# shoeKicking.net
KiCad netlist of a schematic drawn in EAGLE
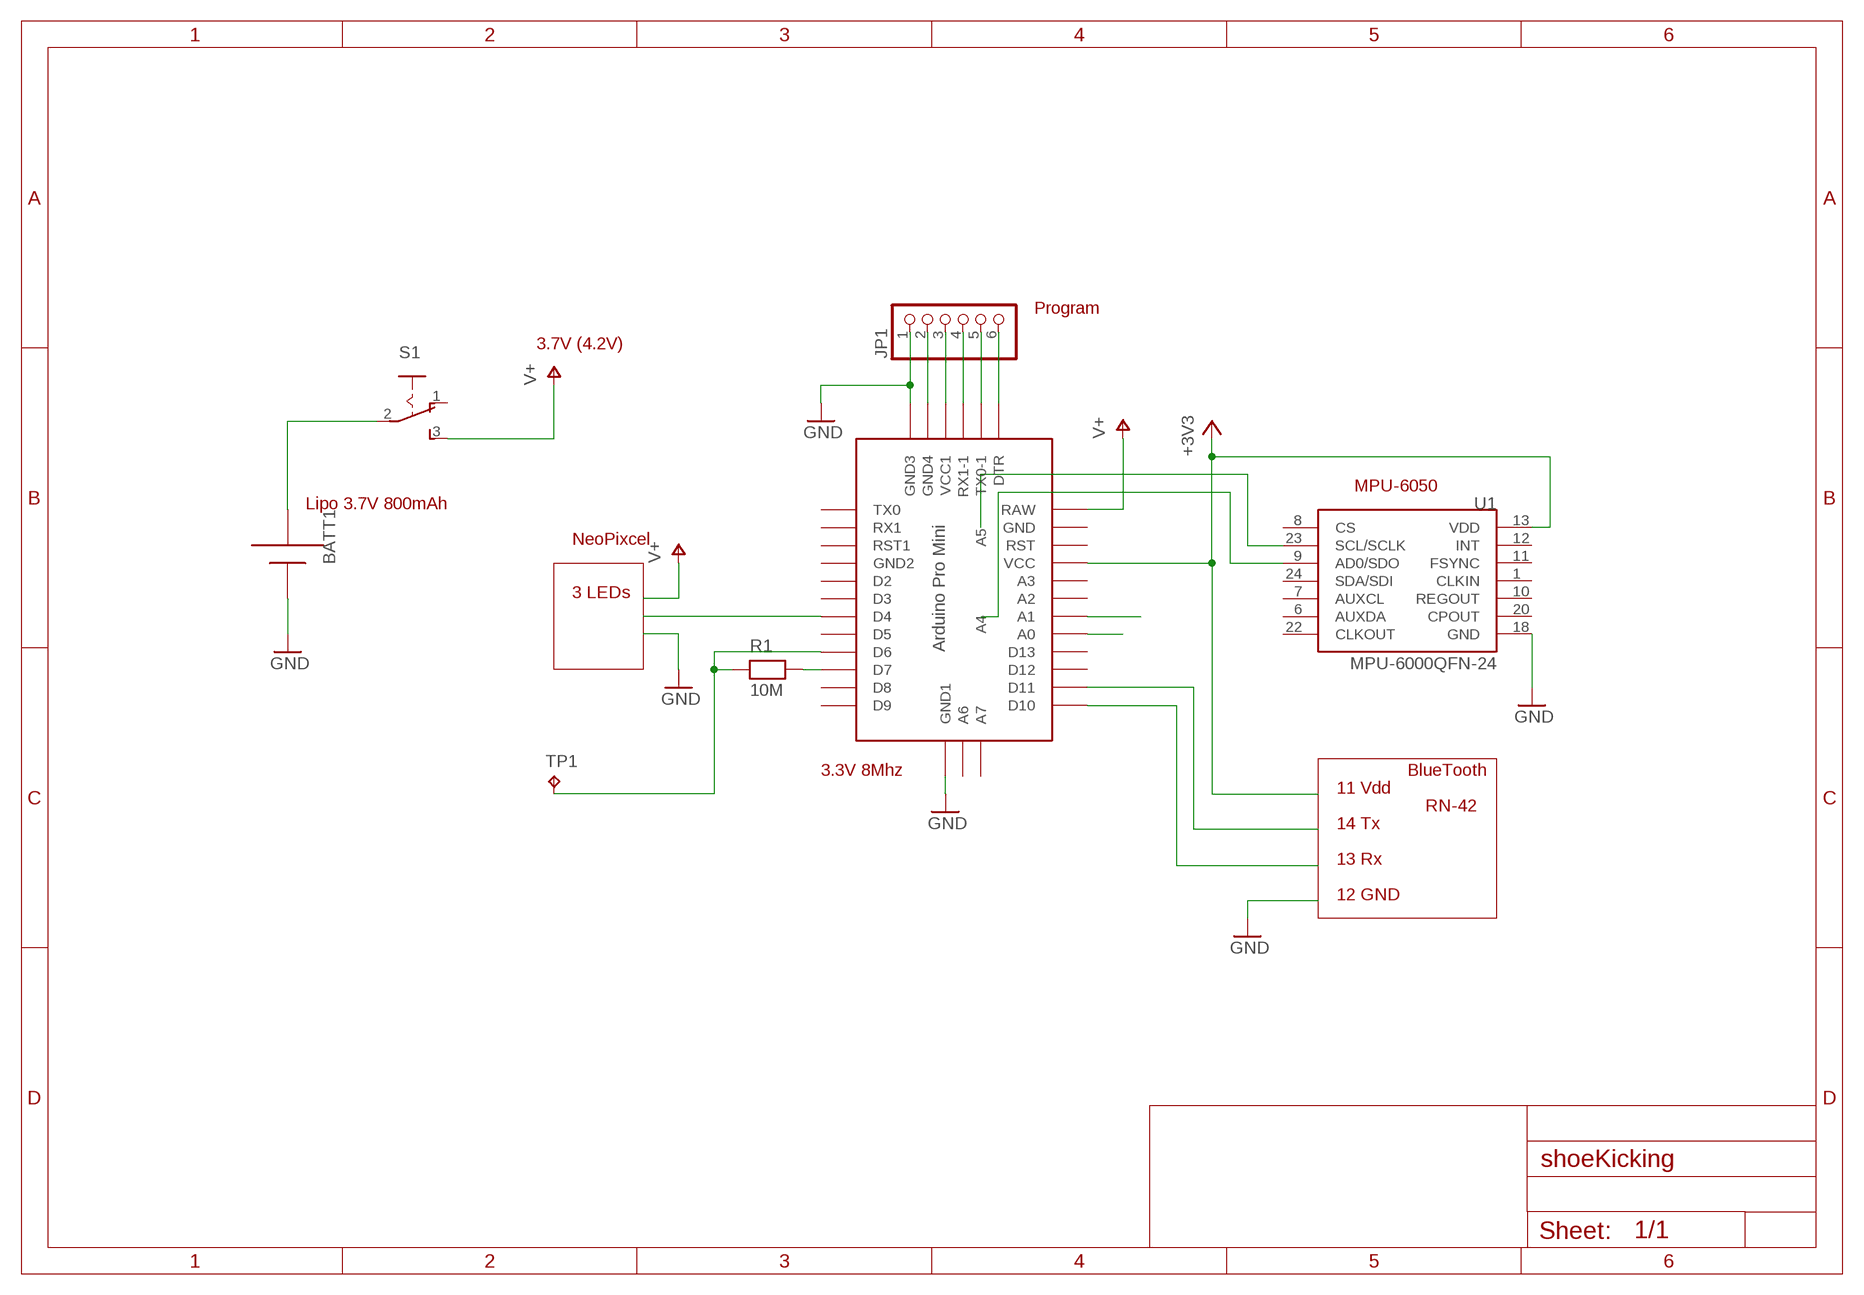
[diagram p0: schematic, sheet 1]

(export (version "E")
  (design (tool "Eeschema 10.0.6"))
  (components
    (comp (ref "BATT1")
      (value "AAA")
      (footprint "eagle-import:12BH412")
      (libsource (lib "eagle-import") (part "AAA"))
    )
    (comp (ref "JP1")
      (value "PINHD-1X6")
      (footprint "eagle-import:1X06")
      (libsource (lib "eagle-import") (part "PINHD-1X6"))
    )
    (comp (ref "R1")
      (value "10M")
      (footprint "eagle-import:R-7,5")
      (libsource (lib "eagle-import") (part "RESEU-7,5"))
    )
    (comp (ref "S1")
      (value "M251")
      (footprint "eagle-import:M251")
      (libsource (lib "eagle-import") (part "M251"))
    )
    (comp (ref "TP1")
      (value "TPB1,27")
      (footprint "eagle-import:B1,27")
      (libsource (lib "eagle-import") (part "TPB1,27"))
    )
    (comp (ref "U$1")
      (value "ABK-PRO-MINI")
      (footprint "eagle-import:ABK-PRO-MINI")
      (libsource (lib "eagle-import") (part "ABK-PRO-MINI"))
    )
    (comp (ref "U1")
      (value "MPU-6000QFN-24")
      (footprint "eagle-import:QFN-24-TESTING")
      (libsource (lib "eagle-import") (part "MPU-6000QFN-24"))
    )
  )
  (nets
    (net (code "1") (name "+3V3") (class "Default")
      (node (ref "U$1") (pin "VCC") (pinfunction "VCC_VCC") (pintype "bidirectional"))
      (node (ref "U1") (pin "13") (pinfunction "VDD_13") (pintype "bidirectional"))
    )
    (net (code "2") (name "GND") (class "Default")
      (node (ref "BATT1") (pin "+") (pinfunction "+_+") (pintype "bidirectional"))
      (node (ref "JP1") (pin "1") (pinfunction "1_1") (pintype "passive"))
      (node (ref "U$1") (pin "GND2") (pinfunction "GND3_GND2") (pintype "bidirectional"))
      (node (ref "U$1") (pin "GND4") (pinfunction "GND1_GND4") (pintype "bidirectional"))
      (node (ref "U1") (pin "18") (pinfunction "GND_18") (pintype "bidirectional"))
    )
    (net (code "3") (name "Net-(JP1-Pad3)") (class "Default")
      (node (ref "JP1") (pin "3") (pinfunction "3_3") (pintype "passive"))
      (node (ref "U$1") (pin "VCC1") (pinfunction "VCC1_VCC1") (pintype "bidirectional"))
    )
    (net (code "4") (name "Net-(JP1-Pad4)") (class "Default")
      (node (ref "JP1") (pin "4") (pinfunction "4_4") (pintype "passive"))
      (node (ref "U$1") (pin "RX1-1") (pinfunction "RX1-1_RX1-1") (pintype "bidirectional"))
    )
    (net (code "5") (name "Net-(JP1-Pad5)") (class "Default")
      (node (ref "JP1") (pin "5") (pinfunction "5_5") (pintype "passive"))
      (node (ref "U$1") (pin "TX0-1") (pinfunction "TX0-1_TX0-1") (pintype "bidirectional"))
    )
    (net (code "6") (name "Net-(JP1-Pad6)") (class "Default")
      (node (ref "JP1") (pin "6") (pinfunction "6_6") (pintype "passive"))
      (node (ref "U$1") (pin "DTR") (pinfunction "DTR_DTR") (pintype "bidirectional"))
    )
    (net (code "7") (name "Net-(R1-Pad1)") (class "Default")
      (node (ref "R1") (pin "1") (pinfunction "1_1") (pintype "passive"))
      (node (ref "TP1") (pin "TP") (pinfunction "TP_TP") (pintype "input"))
      (node (ref "U$1") (pin "D6") (pinfunction "D6_D6") (pintype "bidirectional"))
    )
    (net (code "8") (name "Net-(R1-Pad2)") (class "Default")
      (node (ref "R1") (pin "2") (pinfunction "2_2") (pintype "passive"))
      (node (ref "U$1") (pin "D7") (pinfunction "D7_D7") (pintype "bidirectional"))
    )
    (net (code "9") (name "Net-(S1-P)") (class "Default")
      (node (ref "BATT1") (pin "-") (pinfunction "-_-") (pintype "bidirectional"))
      (node (ref "S1") (pin "2") (pinfunction "P_2") (pintype "passive"))
    )
    (net (code "10") (name "Net-(U$1-GND4)") (class "Default")
      (node (ref "JP1") (pin "2") (pinfunction "2_2") (pintype "passive"))
      (node (ref "U$1") (pin "GND3") (pinfunction "GND4_GND3") (pintype "bidirectional"))
    )
    (net (code "11") (name "V+") (class "Default")
      (node (ref "S1") (pin "3") (pinfunction "S_3") (pintype "passive"))
      (node (ref "U$1") (pin "RAW") (pinfunction "RAW_RAW") (pintype "bidirectional"))
    )
    (net (code "12") (name "unconnected-(S1-O-Pad1)") (class "Default")
      (node (ref "S1") (pin "1") (pinfunction "O_1") (pintype "passive"))
    )
    (net (code "13") (name "unconnected-(U$1-GND2-PadGND1)") (class "Default")
      (node (ref "U$1") (pin "GND1") (pinfunction "GND2_GND1") (pintype "bidirectional"))
    )
    (net (code "14") (name "unconnected-(U$1-PadA0)") (class "Default")
      (node (ref "U$1") (pin "A0") (pinfunction "A0_A0") (pintype "bidirectional"))
    )
    (net (code "15") (name "unconnected-(U$1-PadA1)") (class "Default")
      (node (ref "U$1") (pin "A1") (pinfunction "A1_A1") (pintype "bidirectional"))
    )
    (net (code "16") (name "unconnected-(U$1-PadA2)") (class "Default")
      (node (ref "U$1") (pin "A2") (pinfunction "A2_A2") (pintype "bidirectional"))
    )
    (net (code "17") (name "unconnected-(U$1-PadA3)") (class "Default")
      (node (ref "U$1") (pin "A3") (pinfunction "A3_A3") (pintype "bidirectional"))
    )
    (net (code "18") (name "unconnected-(U$1-PadA4)") (class "Default")
      (node (ref "U$1") (pin "A4") (pinfunction "A4_A4") (pintype "bidirectional"))
    )
    (net (code "19") (name "unconnected-(U$1-PadA5)") (class "Default")
      (node (ref "U$1") (pin "A5") (pinfunction "A5_A5") (pintype "bidirectional"))
    )
    (net (code "20") (name "unconnected-(U$1-PadA6)") (class "Default")
      (node (ref "U$1") (pin "A6") (pinfunction "A6_A6") (pintype "bidirectional"))
    )
    (net (code "21") (name "unconnected-(U$1-PadA7)") (class "Default")
      (node (ref "U$1") (pin "A7") (pinfunction "A7_A7") (pintype "bidirectional"))
    )
    (net (code "22") (name "unconnected-(U$1-PadD2)") (class "Default")
      (node (ref "U$1") (pin "D2") (pinfunction "D2_D2") (pintype "bidirectional"))
    )
    (net (code "23") (name "unconnected-(U$1-PadD3)") (class "Default")
      (node (ref "U$1") (pin "D3") (pinfunction "D3_D3") (pintype "bidirectional"))
    )
    (net (code "24") (name "unconnected-(U$1-PadD4)") (class "Default")
      (node (ref "U$1") (pin "D4") (pinfunction "D4_D4") (pintype "bidirectional"))
    )
    (net (code "25") (name "unconnected-(U$1-PadD5)") (class "Default")
      (node (ref "U$1") (pin "D5") (pinfunction "D5_D5") (pintype "bidirectional"))
    )
    (net (code "26") (name "unconnected-(U$1-PadD8)") (class "Default")
      (node (ref "U$1") (pin "D8") (pinfunction "D8_D8") (pintype "bidirectional"))
    )
    (net (code "27") (name "unconnected-(U$1-PadD9)") (class "Default")
      (node (ref "U$1") (pin "D9") (pinfunction "D9_D9") (pintype "bidirectional"))
    )
    (net (code "28") (name "unconnected-(U$1-PadD10)") (class "Default")
      (node (ref "U$1") (pin "D10") (pinfunction "D10_D10") (pintype "bidirectional"))
    )
    (net (code "29") (name "unconnected-(U$1-PadD11)") (class "Default")
      (node (ref "U$1") (pin "D11") (pinfunction "D11_D11") (pintype "bidirectional"))
    )
    (net (code "30") (name "unconnected-(U$1-PadD12)") (class "Default")
      (node (ref "U$1") (pin "D12") (pinfunction "D12_D12") (pintype "bidirectional"))
    )
    (net (code "31") (name "unconnected-(U$1-PadD13)") (class "Default")
      (node (ref "U$1") (pin "D13") (pinfunction "D13_D13") (pintype "bidirectional"))
    )
    (net (code "32") (name "unconnected-(U$1-PadGND)") (class "Default")
      (node (ref "U$1") (pin "GND") (pinfunction "GND_GND") (pintype "bidirectional"))
    )
    (net (code "33") (name "unconnected-(U$1-PadRST)") (class "Default")
      (node (ref "U$1") (pin "RST") (pinfunction "RST_RST") (pintype "bidirectional"))
    )
    (net (code "34") (name "unconnected-(U$1-PadRST1)") (class "Default")
      (node (ref "U$1") (pin "RST1") (pinfunction "RST1_RST1") (pintype "bidirectional"))
    )
    (net (code "35") (name "unconnected-(U$1-PadRX1)") (class "Default")
      (node (ref "U$1") (pin "RX1") (pinfunction "RX1_RX1") (pintype "bidirectional"))
    )
    (net (code "36") (name "unconnected-(U$1-PadTX0)") (class "Default")
      (node (ref "U$1") (pin "TX0") (pinfunction "TX0_TX0") (pintype "bidirectional"))
    )
    (net (code "37") (name "unconnected-(U1-AD0{slash}SDO-Pad9)") (class "Default")
      (node (ref "U1") (pin "9") (pinfunction "AD0/SDO_9") (pintype "bidirectional"))
    )
    (net (code "38") (name "unconnected-(U1-AUXCL-Pad7)") (class "Default")
      (node (ref "U1") (pin "7") (pinfunction "AUXCL_7") (pintype "bidirectional"))
    )
    (net (code "39") (name "unconnected-(U1-AUXDA-Pad6)") (class "Default")
      (node (ref "U1") (pin "6") (pinfunction "AUXDA_6") (pintype "bidirectional"))
    )
    (net (code "40") (name "unconnected-(U1-CLKIN-Pad1)") (class "Default")
      (node (ref "U1") (pin "1") (pinfunction "CLKIN_1") (pintype "bidirectional"))
    )
    (net (code "41") (name "unconnected-(U1-CLKOUT-Pad22)") (class "Default")
      (node (ref "U1") (pin "22") (pinfunction "CLKOUT_22") (pintype "bidirectional"))
    )
    (net (code "42") (name "unconnected-(U1-CPOUT-Pad20)") (class "Default")
      (node (ref "U1") (pin "20") (pinfunction "CPOUT_20") (pintype "bidirectional"))
    )
    (net (code "43") (name "unconnected-(U1-CS-Pad8)") (class "Default")
      (node (ref "U1") (pin "8") (pinfunction "CS_8") (pintype "bidirectional"))
    )
    (net (code "44") (name "unconnected-(U1-FSYNC-Pad11)") (class "Default")
      (node (ref "U1") (pin "11") (pinfunction "FSYNC_11") (pintype "bidirectional"))
    )
    (net (code "45") (name "unconnected-(U1-INT-Pad12)") (class "Default")
      (node (ref "U1") (pin "12") (pinfunction "INT_12") (pintype "bidirectional"))
    )
    (net (code "46") (name "unconnected-(U1-REGOUT-Pad10)") (class "Default")
      (node (ref "U1") (pin "10") (pinfunction "REGOUT_10") (pintype "bidirectional"))
    )
    (net (code "47") (name "unconnected-(U1-SCL{slash}SCLK-Pad23)") (class "Default")
      (node (ref "U1") (pin "23") (pinfunction "SCL/SCLK_23") (pintype "bidirectional"))
    )
    (net (code "48") (name "unconnected-(U1-SDA{slash}SDI-Pad24)") (class "Default")
      (node (ref "U1") (pin "24") (pinfunction "SDA/SDI_24") (pintype "bidirectional"))
    )
  )
)
